# breakout.net
KiCad netlist of a schematic drawn in EAGLE
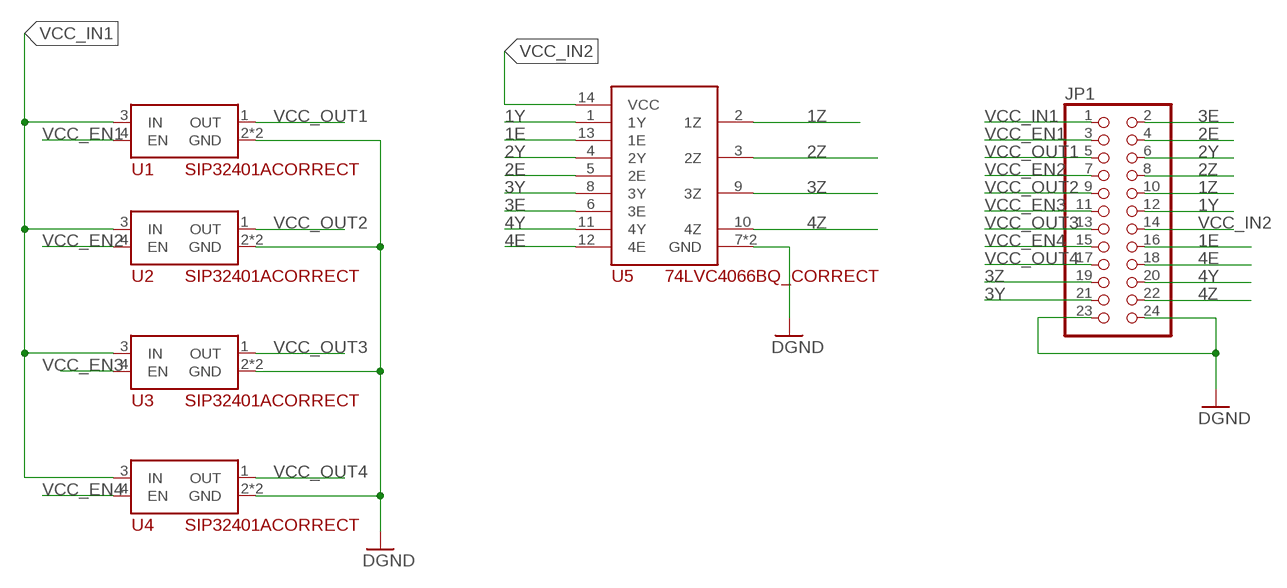
[diagram p0: schematic, sheet 1]

(export (version "E")
  (design (tool "Eeschema 10.0.6"))
  (components
    (comp (ref "JP1")
      (value "PINHD-2X12/90")
      (footprint "eagle-import:2X12_90")
      (libsource (lib "eagle-import") (part "PINHD-2X12/90"))
    )
    (comp (ref "U1")
      (value "SIP32401ACORRECT")
      (footprint "eagle-import:TDFN4_CORRECT")
      (libsource (lib "eagle-import") (part "SIP32401ACORRECT"))
    )
    (comp (ref "U2")
      (value "SIP32401ACORRECT")
      (footprint "eagle-import:TDFN4_CORRECT")
      (libsource (lib "eagle-import") (part "SIP32401ACORRECT"))
    )
    (comp (ref "U3")
      (value "SIP32401ACORRECT")
      (footprint "eagle-import:TDFN4_CORRECT")
      (libsource (lib "eagle-import") (part "SIP32401ACORRECT"))
    )
    (comp (ref "U4")
      (value "SIP32401ACORRECT")
      (footprint "eagle-import:TDFN4_CORRECT")
      (libsource (lib "eagle-import") (part "SIP32401ACORRECT"))
    )
    (comp (ref "U5")
      (value "74LVC4066BQ_CORRECT")
      (footprint "eagle-import:DHVQFN14_CORRECTED")
      (fields (field (name "MANUFACTURER") "Nexperia USA Inc.") (field (name "MPN") "74LVC4066BQ"))
      (libsource (lib "eagle-import") (part "74LVC4066BQ_CORRECT"))
    )
  )
  (nets
    (net (code "1") (name "/1E") (class "Default")
      (node (ref "JP1") (pin "16") (pinfunction "16_16") (pintype "passive"))
      (node (ref "U5") (pin "13") (pinfunction "1E_13") (pintype "input"))
    )
    (net (code "2") (name "/1Y") (class "Default")
      (node (ref "JP1") (pin "12") (pinfunction "12_12") (pintype "passive"))
      (node (ref "U5") (pin "1") (pinfunction "1Y_1") (pintype "bidirectional"))
    )
    (net (code "3") (name "/1Z") (class "Default")
      (node (ref "JP1") (pin "10") (pinfunction "10_10") (pintype "passive"))
      (node (ref "U5") (pin "2") (pinfunction "1Z_2") (pintype "bidirectional"))
    )
    (net (code "4") (name "/2E") (class "Default")
      (node (ref "JP1") (pin "4") (pinfunction "4_4") (pintype "passive"))
      (node (ref "U5") (pin "5") (pinfunction "2E_5") (pintype "input"))
    )
    (net (code "5") (name "/2Y") (class "Default")
      (node (ref "JP1") (pin "6") (pinfunction "6_6") (pintype "passive"))
      (node (ref "U5") (pin "4") (pinfunction "2Y_4") (pintype "bidirectional"))
    )
    (net (code "6") (name "/2Z") (class "Default")
      (node (ref "JP1") (pin "8") (pinfunction "8_8") (pintype "passive"))
      (node (ref "U5") (pin "3") (pinfunction "2Z_3") (pintype "bidirectional"))
    )
    (net (code "7") (name "/3E") (class "Default")
      (node (ref "JP1") (pin "2") (pinfunction "2_2") (pintype "passive"))
      (node (ref "U5") (pin "6") (pinfunction "3E_6") (pintype "input"))
    )
    (net (code "8") (name "/3Y") (class "Default")
      (node (ref "JP1") (pin "21") (pinfunction "21_21") (pintype "passive"))
      (node (ref "U5") (pin "8") (pinfunction "3Y_8") (pintype "bidirectional"))
    )
    (net (code "9") (name "/3Z") (class "Default")
      (node (ref "JP1") (pin "19") (pinfunction "19_19") (pintype "passive"))
      (node (ref "U5") (pin "9") (pinfunction "3Z_9") (pintype "bidirectional"))
    )
    (net (code "10") (name "/4E") (class "Default")
      (node (ref "JP1") (pin "18") (pinfunction "18_18") (pintype "passive"))
      (node (ref "U5") (pin "12") (pinfunction "4E_12") (pintype "input"))
    )
    (net (code "11") (name "/4Y") (class "Default")
      (node (ref "JP1") (pin "20") (pinfunction "20_20") (pintype "passive"))
      (node (ref "U5") (pin "11") (pinfunction "4Y_11") (pintype "bidirectional"))
    )
    (net (code "12") (name "/4Z") (class "Default")
      (node (ref "JP1") (pin "22") (pinfunction "22_22") (pintype "passive"))
      (node (ref "U5") (pin "10") (pinfunction "4Z_10") (pintype "bidirectional"))
    )
    (net (code "13") (name "/VCC_EN1") (class "Default")
      (node (ref "JP1") (pin "3") (pinfunction "3_3") (pintype "passive"))
      (node (ref "U1") (pin "4") (pinfunction "EN_4") (pintype "input"))
    )
    (net (code "14") (name "/VCC_EN2") (class "Default")
      (node (ref "JP1") (pin "7") (pinfunction "7_7") (pintype "passive"))
      (node (ref "U2") (pin "4") (pinfunction "EN_4") (pintype "input"))
    )
    (net (code "15") (name "/VCC_EN3") (class "Default")
      (node (ref "JP1") (pin "11") (pinfunction "11_11") (pintype "passive"))
      (node (ref "U3") (pin "4") (pinfunction "EN_4") (pintype "input"))
    )
    (net (code "16") (name "/VCC_EN4") (class "Default")
      (node (ref "JP1") (pin "15") (pinfunction "15_15") (pintype "passive"))
      (node (ref "U4") (pin "4") (pinfunction "EN_4") (pintype "input"))
    )
    (net (code "17") (name "/VCC_OUT1") (class "Default")
      (node (ref "JP1") (pin "5") (pinfunction "5_5") (pintype "passive"))
      (node (ref "U1") (pin "1") (pinfunction "OUT_1") (pintype "output"))
    )
    (net (code "18") (name "/VCC_OUT2") (class "Default")
      (node (ref "JP1") (pin "9") (pinfunction "9_9") (pintype "passive"))
      (node (ref "U2") (pin "1") (pinfunction "OUT_1") (pintype "output"))
    )
    (net (code "19") (name "/VCC_OUT3") (class "Default")
      (node (ref "JP1") (pin "13") (pinfunction "13_13") (pintype "passive"))
      (node (ref "U3") (pin "1") (pinfunction "OUT_1") (pintype "output"))
    )
    (net (code "20") (name "/VCC_OUT4") (class "Default")
      (node (ref "JP1") (pin "17") (pinfunction "17_17") (pintype "passive"))
      (node (ref "U4") (pin "1") (pinfunction "OUT_1") (pintype "output"))
    )
    (net (code "21") (name "DGND") (class "Default")
      (node (ref "JP1") (pin "23") (pinfunction "23_23") (pintype "passive"))
      (node (ref "JP1") (pin "24") (pinfunction "24_24") (pintype "passive"))
      (node (ref "U1") (pin "2") (pinfunction "GND_2") (pintype "power_in"))
      (node (ref "U1") (pin "PADDLE") (pinfunction "GND_PADDLE") (pintype "power_in"))
      (node (ref "U2") (pin "2") (pinfunction "GND_2") (pintype "power_in"))
      (node (ref "U2") (pin "PADDLE") (pinfunction "GND_PADDLE") (pintype "power_in"))
      (node (ref "U3") (pin "2") (pinfunction "GND_2") (pintype "power_in"))
      (node (ref "U3") (pin "PADDLE") (pinfunction "GND_PADDLE") (pintype "power_in"))
      (node (ref "U4") (pin "2") (pinfunction "GND_2") (pintype "power_in"))
      (node (ref "U4") (pin "PADDLE") (pinfunction "GND_PADDLE") (pintype "power_in"))
      (node (ref "U5") (pin "7") (pinfunction "GND_7") (pintype "power_in"))
      (node (ref "U5") (pin "PADDLE") (pinfunction "GND_PADDLE") (pintype "power_in"))
    )
    (net (code "22") (name "VCC_IN1") (class "Default")
      (node (ref "JP1") (pin "1") (pinfunction "1_1") (pintype "passive"))
      (node (ref "U1") (pin "3") (pinfunction "IN_3") (pintype "input"))
      (node (ref "U2") (pin "3") (pinfunction "IN_3") (pintype "input"))
      (node (ref "U3") (pin "3") (pinfunction "IN_3") (pintype "input"))
      (node (ref "U4") (pin "3") (pinfunction "IN_3") (pintype "input"))
    )
    (net (code "23") (name "VCC_IN2") (class "Default")
      (node (ref "JP1") (pin "14") (pinfunction "14_14") (pintype "passive"))
      (node (ref "U5") (pin "14") (pinfunction "VCC_14") (pintype "power_in"))
    )
  )
)
